# Sheet1.net
KiCad netlist of a schematic drawn in Altium Designer
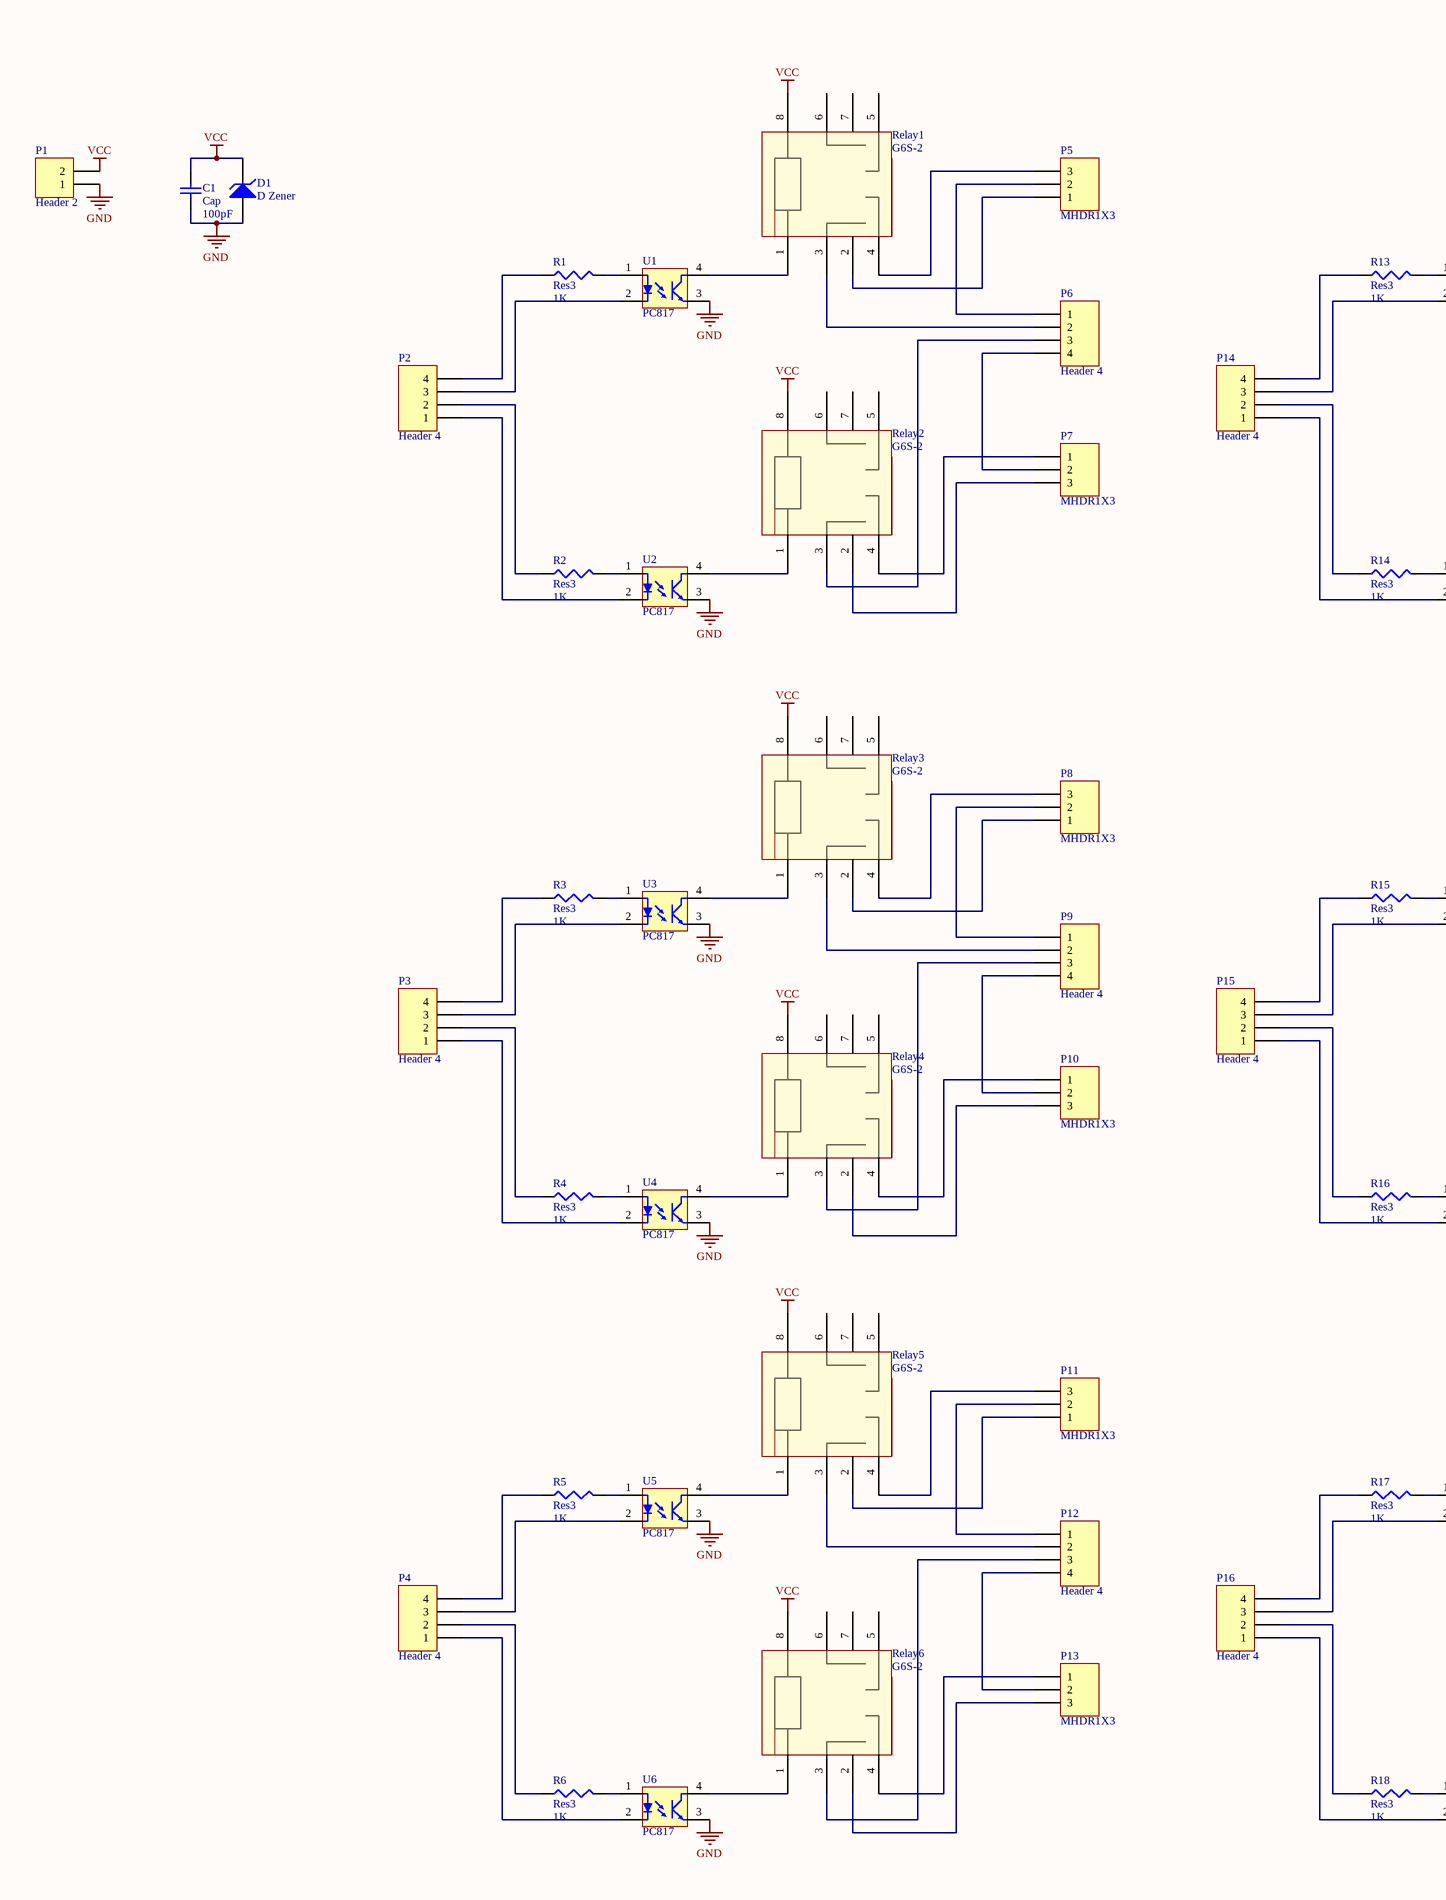
[diagram p0: Sheet1.SchDoc, left]
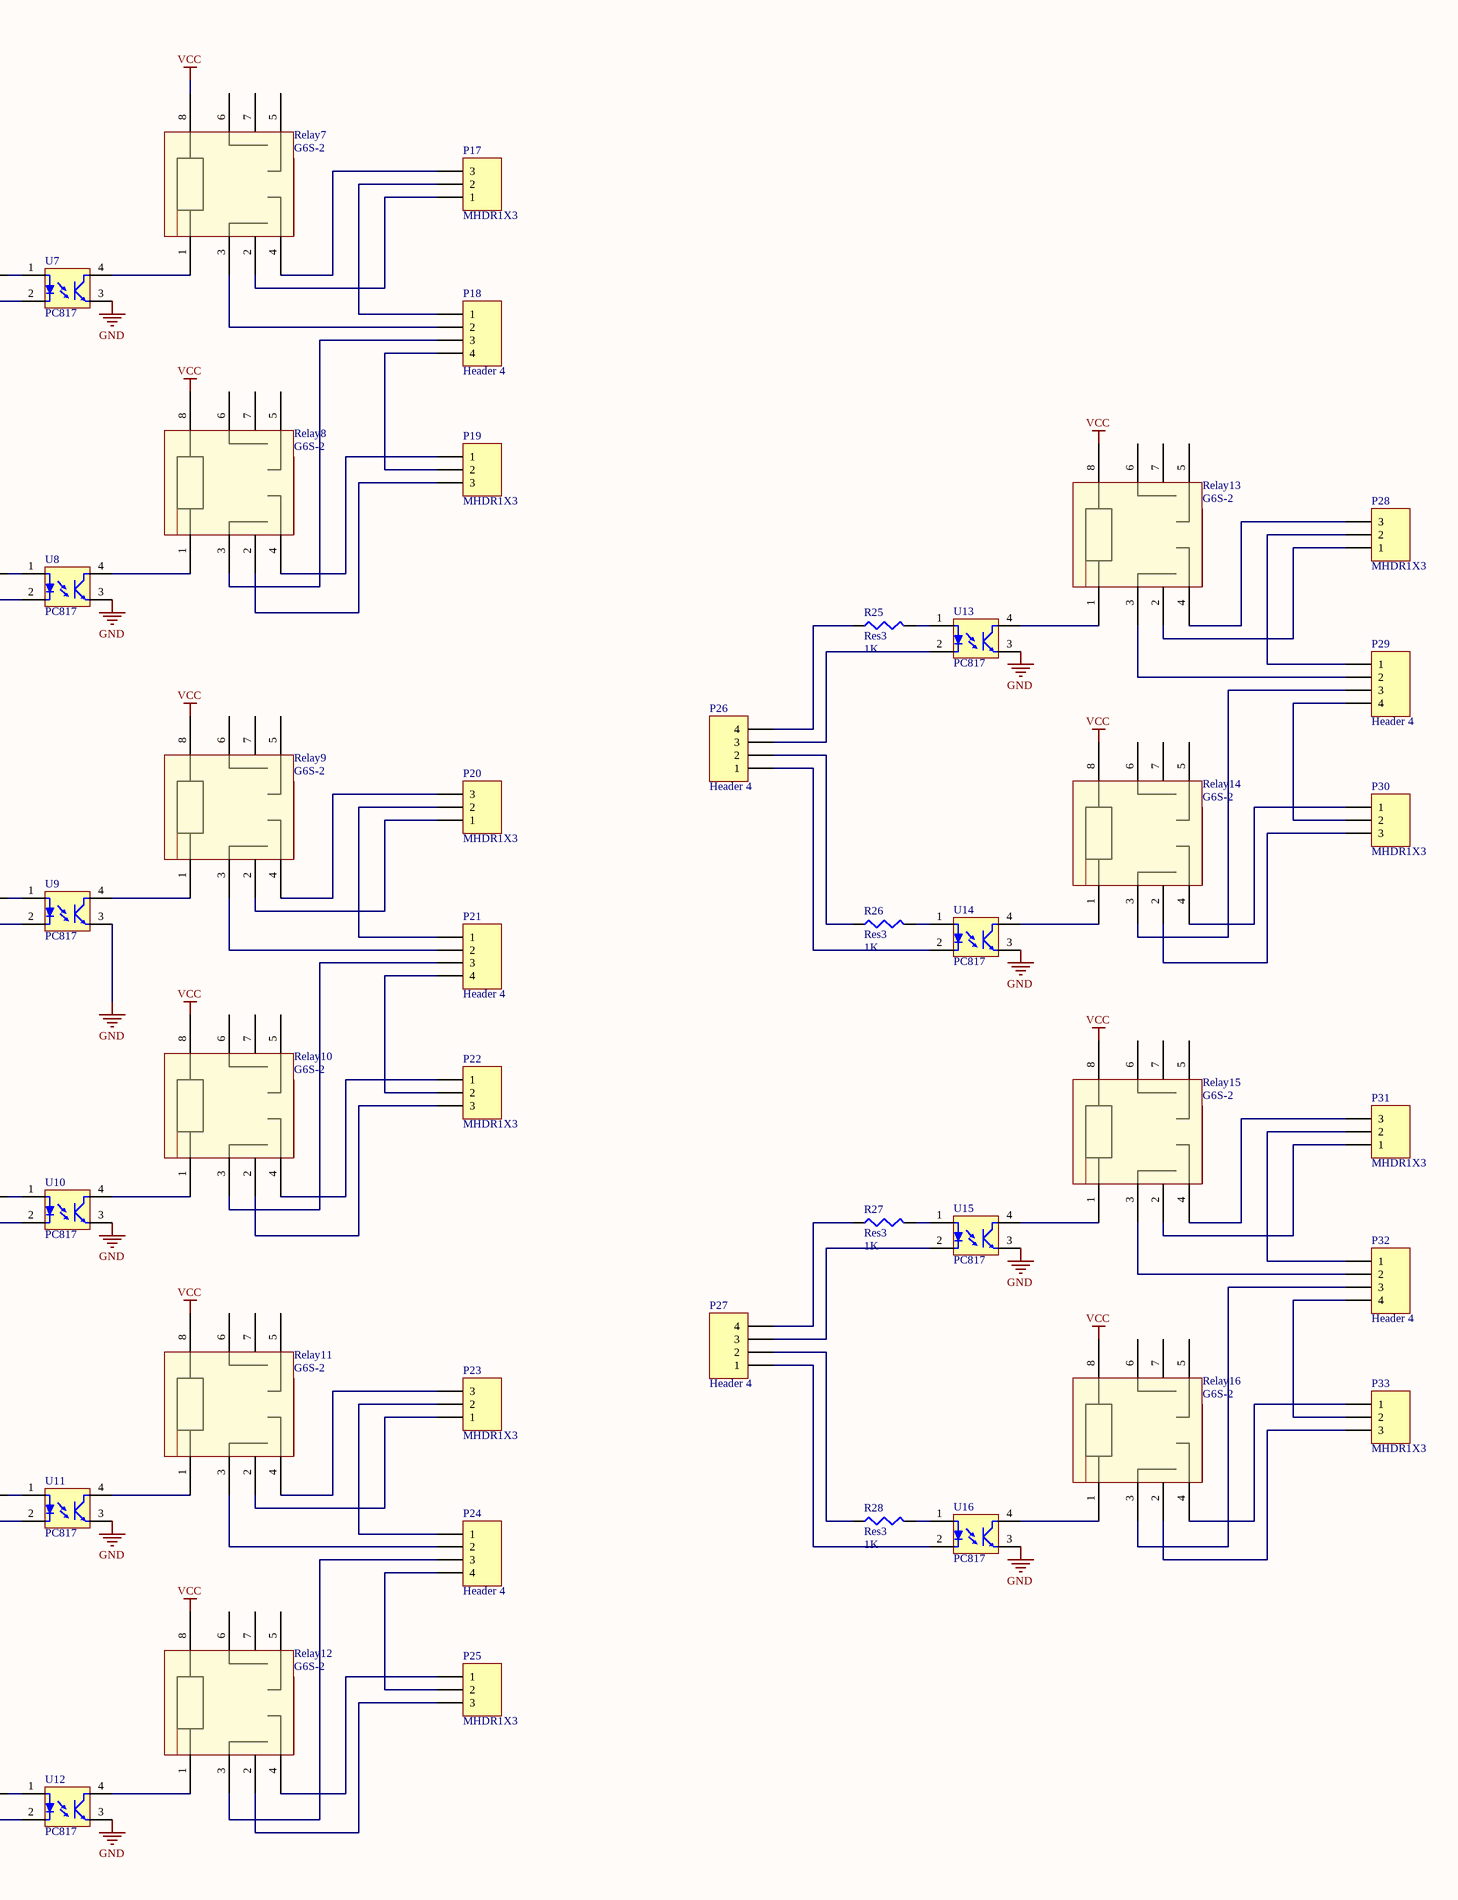
[diagram p1: Sheet1.SchDoc, right]

(export (version "E")
  (design (tool "Eeschema 10.0.6"))
  (components
    (comp (ref "C1")
      (value "Cap")
      (footprint "RAD-0.3")
      (description "Capacitor")
      (fields (field (name "ALTIUM_VALUE") "100pF") (field (name "PUBLISHER") "Altium Limited"))
      (libsource (lib "Miscellaneous Devices") (part "Cap"))
    )
    (comp (ref "D1")
      (value "D Zener")
      (footprint "DIODE-0.7")
      (description "Zener Diode")
      (fields (field (name "PUBLISHER") "Altium Limited"))
      (libsource (lib "Miscellaneous Devices") (part "D Zener"))
    )
    (comp (ref "P1")
      (value "Header 2")
      (footprint "CON2")
      (description "Header, 2-Pin")
      (fields (field (name "PUBLISHER") "Altium Limited"))
      (libsource (lib "Miscellaneous Connectors") (part "Header 2"))
    )
    (comp (ref "P2")
      (value "Header 4")
      (footprint "CON4")
      (description "Header, 4-Pin")
      (fields (field (name "PUBLISHER") "Altium Limited"))
      (libsource (lib "Miscellaneous Connectors") (part "Header 4"))
    )
    (comp (ref "P3")
      (value "Header 4")
      (footprint "CON4")
      (description "Header, 4-Pin")
      (fields (field (name "PUBLISHER") "Altium Limited"))
      (libsource (lib "Miscellaneous Connectors") (part "Header 4"))
    )
    (comp (ref "P4")
      (value "Header 4")
      (footprint "CON4")
      (description "Header, 4-Pin")
      (fields (field (name "PUBLISHER") "Altium Limited"))
      (libsource (lib "Miscellaneous Connectors") (part "Header 4"))
    )
    (comp (ref "P5")
      (value "MHDR1X3")
      (footprint "HDR1X3")
      (description "Header, 3-Pin")
      (fields (field (name "PUBLISHER") "Altium Limited"))
      (libsource (lib "Miscellaneous Connectors") (part "MHDR1X3"))
    )
    (comp (ref "P6")
      (value "Header 4")
      (footprint "CON4")
      (description "Header, 4-Pin")
      (fields (field (name "PUBLISHER") "Altium Limited"))
      (libsource (lib "") (part "Header 4_1"))
    )
    (comp (ref "P7")
      (value "MHDR1X3")
      (footprint "HDR1X3")
      (description "Header, 3-Pin")
      (fields (field (name "PUBLISHER") "Altium Limited"))
      (libsource (lib "") (part "MHDR1X3_1"))
    )
    (comp (ref "P8")
      (value "MHDR1X3")
      (footprint "HDR1X3")
      (description "Header, 3-Pin")
      (fields (field (name "PUBLISHER") "Altium Limited"))
      (libsource (lib "Miscellaneous Connectors") (part "MHDR1X3"))
    )
    (comp (ref "P9")
      (value "Header 4")
      (footprint "CON4")
      (description "Header, 4-Pin")
      (fields (field (name "PUBLISHER") "Altium Limited"))
      (libsource (lib "") (part "Header 4_1"))
    )
    (comp (ref "P10")
      (value "MHDR1X3")
      (footprint "HDR1X3")
      (description "Header, 3-Pin")
      (fields (field (name "PUBLISHER") "Altium Limited"))
      (libsource (lib "") (part "MHDR1X3_1"))
    )
    (comp (ref "P11")
      (value "MHDR1X3")
      (footprint "HDR1X3")
      (description "Header, 3-Pin")
      (fields (field (name "PUBLISHER") "Altium Limited"))
      (libsource (lib "Miscellaneous Connectors") (part "MHDR1X3"))
    )
    (comp (ref "P12")
      (value "Header 4")
      (footprint "CON4")
      (description "Header, 4-Pin")
      (fields (field (name "PUBLISHER") "Altium Limited"))
      (libsource (lib "") (part "Header 4_1"))
    )
    (comp (ref "P13")
      (value "MHDR1X3")
      (footprint "HDR1X3")
      (description "Header, 3-Pin")
      (fields (field (name "PUBLISHER") "Altium Limited"))
      (libsource (lib "") (part "MHDR1X3_1"))
    )
    (comp (ref "P14")
      (value "Header 4")
      (footprint "CON4")
      (description "Header, 4-Pin")
      (fields (field (name "PUBLISHER") "Altium Limited"))
      (libsource (lib "Miscellaneous Connectors") (part "Header 4"))
    )
    (comp (ref "P15")
      (value "Header 4")
      (footprint "CON4")
      (description "Header, 4-Pin")
      (fields (field (name "PUBLISHER") "Altium Limited"))
      (libsource (lib "Miscellaneous Connectors") (part "Header 4"))
    )
    (comp (ref "P16")
      (value "Header 4")
      (footprint "CON4")
      (description "Header, 4-Pin")
      (fields (field (name "PUBLISHER") "Altium Limited"))
      (libsource (lib "Miscellaneous Connectors") (part "Header 4"))
    )
    (comp (ref "P17")
      (value "MHDR1X3")
      (footprint "HDR1X3")
      (description "Header, 3-Pin")
      (fields (field (name "PUBLISHER") "Altium Limited"))
      (libsource (lib "Miscellaneous Connectors") (part "MHDR1X3"))
    )
    (comp (ref "P18")
      (value "Header 4")
      (footprint "CON4")
      (description "Header, 4-Pin")
      (fields (field (name "PUBLISHER") "Altium Limited"))
      (libsource (lib "") (part "Header 4_1"))
    )
    (comp (ref "P19")
      (value "MHDR1X3")
      (footprint "HDR1X3")
      (description "Header, 3-Pin")
      (fields (field (name "PUBLISHER") "Altium Limited"))
      (libsource (lib "") (part "MHDR1X3_1"))
    )
    (comp (ref "P20")
      (value "MHDR1X3")
      (footprint "HDR1X3")
      (description "Header, 3-Pin")
      (fields (field (name "PUBLISHER") "Altium Limited"))
      (libsource (lib "Miscellaneous Connectors") (part "MHDR1X3"))
    )
    (comp (ref "P21")
      (value "Header 4")
      (footprint "CON4")
      (description "Header, 4-Pin")
      (fields (field (name "PUBLISHER") "Altium Limited"))
      (libsource (lib "") (part "Header 4_1"))
    )
    (comp (ref "P22")
      (value "MHDR1X3")
      (footprint "HDR1X3")
      (description "Header, 3-Pin")
      (fields (field (name "PUBLISHER") "Altium Limited"))
      (libsource (lib "") (part "MHDR1X3_1"))
    )
    (comp (ref "P23")
      (value "MHDR1X3")
      (footprint "HDR1X3")
      (description "Header, 3-Pin")
      (fields (field (name "PUBLISHER") "Altium Limited"))
      (libsource (lib "Miscellaneous Connectors") (part "MHDR1X3"))
    )
    (comp (ref "P24")
      (value "Header 4")
      (footprint "CON4")
      (description "Header, 4-Pin")
      (fields (field (name "PUBLISHER") "Altium Limited"))
      (libsource (lib "") (part "Header 4_1"))
    )
    (comp (ref "P25")
      (value "MHDR1X3")
      (footprint "HDR1X3")
      (description "Header, 3-Pin")
      (fields (field (name "PUBLISHER") "Altium Limited"))
      (libsource (lib "") (part "MHDR1X3_1"))
    )
    (comp (ref "P26")
      (value "Header 4")
      (footprint "CON4")
      (description "Header, 4-Pin")
      (fields (field (name "PUBLISHER") "Altium Limited"))
      (libsource (lib "Miscellaneous Connectors") (part "Header 4"))
    )
    (comp (ref "P27")
      (value "Header 4")
      (footprint "CON4")
      (description "Header, 4-Pin")
      (fields (field (name "PUBLISHER") "Altium Limited"))
      (libsource (lib "Miscellaneous Connectors") (part "Header 4"))
    )
    (comp (ref "P28")
      (value "MHDR1X3")
      (footprint "HDR1X3")
      (description "Header, 3-Pin")
      (fields (field (name "PUBLISHER") "Altium Limited"))
      (libsource (lib "Miscellaneous Connectors") (part "MHDR1X3"))
    )
    (comp (ref "P29")
      (value "Header 4")
      (footprint "CON4")
      (description "Header, 4-Pin")
      (fields (field (name "PUBLISHER") "Altium Limited"))
      (libsource (lib "") (part "Header 4_1"))
    )
    (comp (ref "P30")
      (value "MHDR1X3")
      (footprint "HDR1X3")
      (description "Header, 3-Pin")
      (fields (field (name "PUBLISHER") "Altium Limited"))
      (libsource (lib "") (part "MHDR1X3_1"))
    )
    (comp (ref "P31")
      (value "MHDR1X3")
      (footprint "HDR1X3")
      (description "Header, 3-Pin")
      (fields (field (name "PUBLISHER") "Altium Limited"))
      (libsource (lib "Miscellaneous Connectors") (part "MHDR1X3"))
    )
    (comp (ref "P32")
      (value "Header 4")
      (footprint "CON4")
      (description "Header, 4-Pin")
      (fields (field (name "PUBLISHER") "Altium Limited"))
      (libsource (lib "") (part "Header 4_1"))
    )
    (comp (ref "P33")
      (value "MHDR1X3")
      (footprint "HDR1X3")
      (description "Header, 3-Pin")
      (fields (field (name "PUBLISHER") "Altium Limited"))
      (libsource (lib "") (part "MHDR1X3_1"))
    )
    (comp (ref "R1")
      (value "Res3")
      (footprint "R1/4W")
      (description "Resistor")
      (fields (field (name "ALTIUM_VALUE") "1K") (field (name "PUBLISHER") "Altium Limited"))
      (libsource (lib "Miscellaneous Devices") (part "Res3"))
    )
    (comp (ref "R2")
      (value "Res3")
      (footprint "R1/4W")
      (description "Resistor")
      (fields (field (name "ALTIUM_VALUE") "1K") (field (name "PUBLISHER") "Altium Limited"))
      (libsource (lib "Miscellaneous Devices") (part "Res3"))
    )
    (comp (ref "R3")
      (value "Res3")
      (footprint "R1/4W")
      (description "Resistor")
      (fields (field (name "ALTIUM_VALUE") "1K") (field (name "PUBLISHER") "Altium Limited"))
      (libsource (lib "Miscellaneous Devices") (part "Res3"))
    )
    (comp (ref "R4")
      (value "Res3")
      (footprint "R1/4W")
      (description "Resistor")
      (fields (field (name "ALTIUM_VALUE") "1K") (field (name "PUBLISHER") "Altium Limited"))
      (libsource (lib "Miscellaneous Devices") (part "Res3"))
    )
    (comp (ref "R5")
      (value "Res3")
      (footprint "R1/4W")
      (description "Resistor")
      (fields (field (name "ALTIUM_VALUE") "1K") (field (name "PUBLISHER") "Altium Limited"))
      (libsource (lib "Miscellaneous Devices") (part "Res3"))
    )
    (comp (ref "R6")
      (value "Res3")
      (footprint "R1/4W")
      (description "Resistor")
      (fields (field (name "ALTIUM_VALUE") "1K") (field (name "PUBLISHER") "Altium Limited"))
      (libsource (lib "Miscellaneous Devices") (part "Res3"))
    )
    (comp (ref "R13")
      (value "Res3")
      (footprint "R1/4W")
      (description "Resistor")
      (fields (field (name "ALTIUM_VALUE") "1K") (field (name "PUBLISHER") "Altium Limited"))
      (libsource (lib "Miscellaneous Devices") (part "Res3"))
    )
    (comp (ref "R14")
      (value "Res3")
      (footprint "R1/4W")
      (description "Resistor")
      (fields (field (name "ALTIUM_VALUE") "1K") (field (name "PUBLISHER") "Altium Limited"))
      (libsource (lib "Miscellaneous Devices") (part "Res3"))
    )
    (comp (ref "R15")
      (value "Res3")
      (footprint "R1/4W")
      (description "Resistor")
      (fields (field (name "ALTIUM_VALUE") "1K") (field (name "PUBLISHER") "Altium Limited"))
      (libsource (lib "Miscellaneous Devices") (part "Res3"))
    )
    (comp (ref "R16")
      (value "Res3")
      (footprint "R1/4W")
      (description "Resistor")
      (fields (field (name "ALTIUM_VALUE") "1K") (field (name "PUBLISHER") "Altium Limited"))
      (libsource (lib "Miscellaneous Devices") (part "Res3"))
    )
    (comp (ref "R17")
      (value "Res3")
      (footprint "R1/4W")
      (description "Resistor")
      (fields (field (name "ALTIUM_VALUE") "1K") (field (name "PUBLISHER") "Altium Limited"))
      (libsource (lib "Miscellaneous Devices") (part "Res3"))
    )
    (comp (ref "R18")
      (value "Res3")
      (footprint "R1/4W")
      (description "Resistor")
      (fields (field (name "ALTIUM_VALUE") "1K") (field (name "PUBLISHER") "Altium Limited"))
      (libsource (lib "Miscellaneous Devices") (part "Res3"))
    )
    (comp (ref "R25")
      (value "Res3")
      (footprint "R1/4W")
      (description "Resistor")
      (fields (field (name "ALTIUM_VALUE") "1K") (field (name "PUBLISHER") "Altium Limited"))
      (libsource (lib "Miscellaneous Devices") (part "Res3"))
    )
    (comp (ref "R26")
      (value "Res3")
      (footprint "R1/4W")
      (description "Resistor")
      (fields (field (name "ALTIUM_VALUE") "1K") (field (name "PUBLISHER") "Altium Limited"))
      (libsource (lib "Miscellaneous Devices") (part "Res3"))
    )
    (comp (ref "R27")
      (value "Res3")
      (footprint "R1/4W")
      (description "Resistor")
      (fields (field (name "ALTIUM_VALUE") "1K") (field (name "PUBLISHER") "Altium Limited"))
      (libsource (lib "Miscellaneous Devices") (part "Res3"))
    )
    (comp (ref "R28")
      (value "Res3")
      (footprint "R1/4W")
      (description "Resistor")
      (fields (field (name "ALTIUM_VALUE") "1K") (field (name "PUBLISHER") "Altium Limited"))
      (libsource (lib "Miscellaneous Devices") (part "Res3"))
    )
    (comp (ref "Relay1")
      (value "G6S-2")
      (footprint "G6S-2")
      (libsource (lib "dung_maker_2018") (part "G6S-2"))
    )
    (comp (ref "Relay2")
      (value "G6S-2")
      (footprint "G6S-2")
      (libsource (lib "dung_maker_2018") (part "G6S-2"))
    )
    (comp (ref "Relay3")
      (value "G6S-2")
      (footprint "G6S-2")
      (libsource (lib "dung_maker_2018") (part "G6S-2"))
    )
    (comp (ref "Relay4")
      (value "G6S-2")
      (footprint "G6S-2")
      (libsource (lib "dung_maker_2018") (part "G6S-2"))
    )
    (comp (ref "Relay5")
      (value "G6S-2")
      (footprint "G6S-2")
      (libsource (lib "dung_maker_2018") (part "G6S-2"))
    )
    (comp (ref "Relay6")
      (value "G6S-2")
      (footprint "G6S-2")
      (libsource (lib "dung_maker_2018") (part "G6S-2"))
    )
    (comp (ref "Relay7")
      (value "G6S-2")
      (footprint "G6S-2")
      (libsource (lib "dung_maker_2018") (part "G6S-2"))
    )
    (comp (ref "Relay8")
      (value "G6S-2")
      (footprint "G6S-2")
      (libsource (lib "dung_maker_2018") (part "G6S-2"))
    )
    (comp (ref "Relay9")
      (value "G6S-2")
      (footprint "G6S-2")
      (libsource (lib "dung_maker_2018") (part "G6S-2"))
    )
    (comp (ref "Relay10")
      (value "G6S-2")
      (footprint "G6S-2")
      (libsource (lib "dung_maker_2018") (part "G6S-2"))
    )
    (comp (ref "Relay11")
      (value "G6S-2")
      (footprint "G6S-2")
      (libsource (lib "dung_maker_2018") (part "G6S-2"))
    )
    (comp (ref "Relay12")
      (value "G6S-2")
      (footprint "G6S-2")
      (libsource (lib "dung_maker_2018") (part "G6S-2"))
    )
    (comp (ref "Relay13")
      (value "G6S-2")
      (footprint "G6S-2")
      (libsource (lib "dung_maker_2018") (part "G6S-2"))
    )
    (comp (ref "Relay14")
      (value "G6S-2")
      (footprint "G6S-2")
      (libsource (lib "dung_maker_2018") (part "G6S-2"))
    )
    (comp (ref "Relay15")
      (value "G6S-2")
      (footprint "G6S-2")
      (libsource (lib "dung_maker_2018") (part "G6S-2"))
    )
    (comp (ref "Relay16")
      (value "G6S-2")
      (footprint "G6S-2")
      (libsource (lib "dung_maker_2018") (part "G6S-2"))
    )
    (comp (ref "U1")
      (value "PC817")
      (footprint "DIP4")
      (fields (field (name "Comment") "OPTO"))
      (libsource (lib "dung_maker_2018") (part "OPTO_PC817"))
    )
    (comp (ref "U2")
      (value "PC817")
      (footprint "DIP4")
      (fields (field (name "Comment") "OPTO"))
      (libsource (lib "dung_maker_2018") (part "OPTO_PC817"))
    )
    (comp (ref "U3")
      (value "PC817")
      (footprint "DIP4")
      (fields (field (name "Comment") "OPTO"))
      (libsource (lib "dung_maker_2018") (part "OPTO_PC817"))
    )
    (comp (ref "U4")
      (value "PC817")
      (footprint "DIP4")
      (fields (field (name "Comment") "OPTO"))
      (libsource (lib "dung_maker_2018") (part "OPTO_PC817"))
    )
    (comp (ref "U5")
      (value "PC817")
      (footprint "DIP4")
      (fields (field (name "Comment") "OPTO"))
      (libsource (lib "dung_maker_2018") (part "OPTO_PC817"))
    )
    (comp (ref "U6")
      (value "PC817")
      (footprint "DIP4")
      (fields (field (name "Comment") "OPTO"))
      (libsource (lib "dung_maker_2018") (part "OPTO_PC817"))
    )
    (comp (ref "U7")
      (value "PC817")
      (footprint "DIP4")
      (fields (field (name "Comment") "OPTO"))
      (libsource (lib "dung_maker_2018") (part "OPTO_PC817"))
    )
    (comp (ref "U8")
      (value "PC817")
      (footprint "DIP4")
      (fields (field (name "Comment") "OPTO"))
      (libsource (lib "dung_maker_2018") (part "OPTO_PC817"))
    )
    (comp (ref "U9")
      (value "PC817")
      (footprint "DIP4")
      (fields (field (name "Comment") "OPTO"))
      (libsource (lib "dung_maker_2018") (part "OPTO_PC817"))
    )
    (comp (ref "U10")
      (value "PC817")
      (footprint "DIP4")
      (fields (field (name "Comment") "OPTO"))
      (libsource (lib "dung_maker_2018") (part "OPTO_PC817"))
    )
    (comp (ref "U11")
      (value "PC817")
      (footprint "DIP4")
      (fields (field (name "Comment") "OPTO"))
      (libsource (lib "dung_maker_2018") (part "OPTO_PC817"))
    )
    (comp (ref "U12")
      (value "PC817")
      (footprint "DIP4")
      (fields (field (name "Comment") "OPTO"))
      (libsource (lib "dung_maker_2018") (part "OPTO_PC817"))
    )
    (comp (ref "U13")
      (value "PC817")
      (footprint "DIP4")
      (fields (field (name "Comment") "OPTO"))
      (libsource (lib "dung_maker_2018") (part "OPTO_PC817"))
    )
    (comp (ref "U14")
      (value "PC817")
      (footprint "DIP4")
      (fields (field (name "Comment") "OPTO"))
      (libsource (lib "dung_maker_2018") (part "OPTO_PC817"))
    )
    (comp (ref "U15")
      (value "PC817")
      (footprint "DIP4")
      (fields (field (name "Comment") "OPTO"))
      (libsource (lib "dung_maker_2018") (part "OPTO_PC817"))
    )
    (comp (ref "U16")
      (value "PC817")
      (footprint "DIP4")
      (fields (field (name "Comment") "OPTO"))
      (libsource (lib "dung_maker_2018") (part "OPTO_PC817"))
    )
  )
  (nets
    (net (code "1") (name "GND") (class "Default")
      (node (ref "C1") (pin "1") (pinfunction "1_1") (pintype "passive"))
      (node (ref "D1") (pin "1") (pinfunction "A_1") (pintype "passive"))
      (node (ref "P1") (pin "1") (pinfunction "1_1") (pintype "passive"))
      (node (ref "U1") (pin "3") (pinfunction "E_3") (pintype "passive"))
      (node (ref "U10") (pin "3") (pinfunction "E_3") (pintype "passive"))
      (node (ref "U11") (pin "3") (pinfunction "E_3") (pintype "passive"))
      (node (ref "U12") (pin "3") (pinfunction "E_3") (pintype "passive"))
      (node (ref "U13") (pin "3") (pinfunction "E_3") (pintype "passive"))
      (node (ref "U14") (pin "3") (pinfunction "E_3") (pintype "passive"))
      (node (ref "U15") (pin "3") (pinfunction "E_3") (pintype "passive"))
      (node (ref "U16") (pin "3") (pinfunction "E_3") (pintype "passive"))
      (node (ref "U2") (pin "3") (pinfunction "E_3") (pintype "passive"))
      (node (ref "U3") (pin "3") (pinfunction "E_3") (pintype "passive"))
      (node (ref "U4") (pin "3") (pinfunction "E_3") (pintype "passive"))
      (node (ref "U5") (pin "3") (pinfunction "E_3") (pintype "passive"))
      (node (ref "U6") (pin "3") (pinfunction "E_3") (pintype "passive"))
      (node (ref "U7") (pin "3") (pinfunction "E_3") (pintype "passive"))
      (node (ref "U8") (pin "3") (pinfunction "E_3") (pintype "passive"))
      (node (ref "U9") (pin "3") (pinfunction "E_3") (pintype "passive"))
    )
    (net (code "2") (name "Net-(P2-Pad1)") (class "Default")
      (node (ref "P2") (pin "1") (pinfunction "1_1") (pintype "passive"))
      (node (ref "U2") (pin "2") (pinfunction "C_2") (pintype "passive"))
    )
    (net (code "3") (name "Net-(P2-Pad2)") (class "Default")
      (node (ref "P2") (pin "2") (pinfunction "2_2") (pintype "passive"))
      (node (ref "R2") (pin "1") (pinfunction "1_1") (pintype "passive"))
    )
    (net (code "4") (name "Net-(P2-Pad3)") (class "Default")
      (node (ref "P2") (pin "3") (pinfunction "3_3") (pintype "passive"))
      (node (ref "U1") (pin "2") (pinfunction "C_2") (pintype "passive"))
    )
    (net (code "5") (name "Net-(P2-Pad4)") (class "Default")
      (node (ref "P2") (pin "4") (pinfunction "4_4") (pintype "passive"))
      (node (ref "R1") (pin "1") (pinfunction "1_1") (pintype "passive"))
    )
    (net (code "6") (name "Net-(P3-Pad1)") (class "Default")
      (node (ref "P3") (pin "1") (pinfunction "1_1") (pintype "passive"))
      (node (ref "U4") (pin "2") (pinfunction "C_2") (pintype "passive"))
    )
    (net (code "7") (name "Net-(P3-Pad2)") (class "Default")
      (node (ref "P3") (pin "2") (pinfunction "2_2") (pintype "passive"))
      (node (ref "R4") (pin "1") (pinfunction "1_1") (pintype "passive"))
    )
    (net (code "8") (name "Net-(P3-Pad3)") (class "Default")
      (node (ref "P3") (pin "3") (pinfunction "3_3") (pintype "passive"))
      (node (ref "U3") (pin "2") (pinfunction "C_2") (pintype "passive"))
    )
    (net (code "9") (name "Net-(P3-Pad4)") (class "Default")
      (node (ref "P3") (pin "4") (pinfunction "4_4") (pintype "passive"))
      (node (ref "R3") (pin "1") (pinfunction "1_1") (pintype "passive"))
    )
    (net (code "10") (name "Net-(P4-Pad1)") (class "Default")
      (node (ref "P4") (pin "1") (pinfunction "1_1") (pintype "passive"))
      (node (ref "U6") (pin "2") (pinfunction "C_2") (pintype "passive"))
    )
    (net (code "11") (name "Net-(P4-Pad2)") (class "Default")
      (node (ref "P4") (pin "2") (pinfunction "2_2") (pintype "passive"))
      (node (ref "R6") (pin "1") (pinfunction "1_1") (pintype "passive"))
    )
    (net (code "12") (name "Net-(P4-Pad3)") (class "Default")
      (node (ref "P4") (pin "3") (pinfunction "3_3") (pintype "passive"))
      (node (ref "U5") (pin "2") (pinfunction "C_2") (pintype "passive"))
    )
    (net (code "13") (name "Net-(P4-Pad4)") (class "Default")
      (node (ref "P4") (pin "4") (pinfunction "4_4") (pintype "passive"))
      (node (ref "R5") (pin "1") (pinfunction "1_1") (pintype "passive"))
    )
    (net (code "14") (name "Net-(P5-Pad2)") (class "Default")
      (node (ref "P5") (pin "2") (pinfunction "2_2") (pintype "passive"))
      (node (ref "P6") (pin "1") (pinfunction "1_1") (pintype "passive"))
    )
    (net (code "15") (name "Net-(P6-Pad2)") (class "Default")
      (node (ref "P6") (pin "2") (pinfunction "2_2") (pintype "passive"))
      (node (ref "Relay1") (pin "3") (pinfunction "3_3") (pintype "passive"))
    )
    (net (code "16") (name "Net-(P6-Pad3)") (class "Default")
      (node (ref "P6") (pin "3") (pinfunction "3_3") (pintype "passive"))
      (node (ref "Relay2") (pin "3") (pinfunction "3_3") (pintype "passive"))
    )
    (net (code "17") (name "Net-(P6-Pad4)") (class "Default")
      (node (ref "P6") (pin "4") (pinfunction "4_4") (pintype "passive"))
      (node (ref "P7") (pin "2") (pinfunction "2_2") (pintype "passive"))
    )
    (net (code "18") (name "Net-(P8-Pad2)") (class "Default")
      (node (ref "P8") (pin "2") (pinfunction "2_2") (pintype "passive"))
      (node (ref "P9") (pin "1") (pinfunction "1_1") (pintype "passive"))
    )
    (net (code "19") (name "Net-(P9-Pad2)") (class "Default")
      (node (ref "P9") (pin "2") (pinfunction "2_2") (pintype "passive"))
      (node (ref "Relay3") (pin "3") (pinfunction "3_3") (pintype "passive"))
    )
    (net (code "20") (name "Net-(P9-Pad3)") (class "Default")
      (node (ref "P9") (pin "3") (pinfunction "3_3") (pintype "passive"))
      (node (ref "Relay4") (pin "3") (pinfunction "3_3") (pintype "passive"))
    )
    (net (code "21") (name "Net-(P10-Pad2)") (class "Default")
      (node (ref "P10") (pin "2") (pinfunction "2_2") (pintype "passive"))
      (node (ref "P9") (pin "4") (pinfunction "4_4") (pintype "passive"))
    )
    (net (code "22") (name "Net-(P11-Pad2)") (class "Default")
      (node (ref "P11") (pin "2") (pinfunction "2_2") (pintype "passive"))
      (node (ref "P12") (pin "1") (pinfunction "1_1") (pintype "passive"))
    )
    (net (code "23") (name "Net-(P12-Pad2)") (class "Default")
      (node (ref "P12") (pin "2") (pinfunction "2_2") (pintype "passive"))
      (node (ref "Relay5") (pin "3") (pinfunction "3_3") (pintype "passive"))
    )
    (net (code "24") (name "Net-(P12-Pad3)") (class "Default")
      (node (ref "P12") (pin "3") (pinfunction "3_3") (pintype "passive"))
      (node (ref "Relay6") (pin "3") (pinfunction "3_3") (pintype "passive"))
    )
    (net (code "25") (name "Net-(P12-Pad4)") (class "Default")
      (node (ref "P12") (pin "4") (pinfunction "4_4") (pintype "passive"))
      (node (ref "P13") (pin "2") (pinfunction "2_2") (pintype "passive"))
    )
    (net (code "26") (name "Net-(P14-Pad1)") (class "Default")
      (node (ref "P14") (pin "1") (pinfunction "1_1") (pintype "passive"))
      (node (ref "U8") (pin "2") (pinfunction "C_2") (pintype "passive"))
    )
    (net (code "27") (name "Net-(P14-Pad2)") (class "Default")
      (node (ref "P14") (pin "2") (pinfunction "2_2") (pintype "passive"))
      (node (ref "R14") (pin "1") (pinfunction "1_1") (pintype "passive"))
    )
    (net (code "28") (name "Net-(P14-Pad3)") (class "Default")
      (node (ref "P14") (pin "3") (pinfunction "3_3") (pintype "passive"))
      (node (ref "U7") (pin "2") (pinfunction "C_2") (pintype "passive"))
    )
    (net (code "29") (name "Net-(P14-Pad4)") (class "Default")
      (node (ref "P14") (pin "4") (pinfunction "4_4") (pintype "passive"))
      (node (ref "R13") (pin "1") (pinfunction "1_1") (pintype "passive"))
    )
    (net (code "30") (name "Net-(P15-Pad1)") (class "Default")
      (node (ref "P15") (pin "1") (pinfunction "1_1") (pintype "passive"))
      (node (ref "U10") (pin "2") (pinfunction "C_2") (pintype "passive"))
    )
    (net (code "31") (name "Net-(P15-Pad2)") (class "Default")
      (node (ref "P15") (pin "2") (pinfunction "2_2") (pintype "passive"))
      (node (ref "R16") (pin "1") (pinfunction "1_1") (pintype "passive"))
    )
    (net (code "32") (name "Net-(P15-Pad3)") (class "Default")
      (node (ref "P15") (pin "3") (pinfunction "3_3") (pintype "passive"))
      (node (ref "U9") (pin "2") (pinfunction "C_2") (pintype "passive"))
    )
    (net (code "33") (name "Net-(P15-Pad4)") (class "Default")
      (node (ref "P15") (pin "4") (pinfunction "4_4") (pintype "passive"))
      (node (ref "R15") (pin "1") (pinfunction "1_1") (pintype "passive"))
    )
    (net (code "34") (name "Net-(P16-Pad1)") (class "Default")
      (node (ref "P16") (pin "1") (pinfunction "1_1") (pintype "passive"))
      (node (ref "U12") (pin "2") (pinfunction "C_2") (pintype "passive"))
    )
    (net (code "35") (name "Net-(P16-Pad2)") (class "Default")
      (node (ref "P16") (pin "2") (pinfunction "2_2") (pintype "passive"))
      (node (ref "R18") (pin "1") (pinfunction "1_1") (pintype "passive"))
    )
    (net (code "36") (name "Net-(P16-Pad3)") (class "Default")
      (node (ref "P16") (pin "3") (pinfunction "3_3") (pintype "passive"))
      (node (ref "U11") (pin "2") (pinfunction "C_2") (pintype "passive"))
    )
    (net (code "37") (name "Net-(P16-Pad4)") (class "Default")
      (node (ref "P16") (pin "4") (pinfunction "4_4") (pintype "passive"))
      (node (ref "R17") (pin "1") (pinfunction "1_1") (pintype "passive"))
    )
    (net (code "38") (name "Net-(P17-Pad2)") (class "Default")
      (node (ref "P17") (pin "2") (pinfunction "2_2") (pintype "passive"))
      (node (ref "P18") (pin "1") (pinfunction "1_1") (pintype "passive"))
    )
    (net (code "39") (name "Net-(P18-Pad2)") (class "Default")
      (node (ref "P18") (pin "2") (pinfunction "2_2") (pintype "passive"))
      (node (ref "Relay7") (pin "3") (pinfunction "3_3") (pintype "passive"))
    )
    (net (code "40") (name "Net-(P18-Pad3)") (class "Default")
      (node (ref "P18") (pin "3") (pinfunction "3_3") (pintype "passive"))
      (node (ref "Relay8") (pin "3") (pinfunction "3_3") (pintype "passive"))
    )
    (net (code "41") (name "Net-(P18-Pad4)") (class "Default")
      (node (ref "P18") (pin "4") (pinfunction "4_4") (pintype "passive"))
      (node (ref "P19") (pin "2") (pinfunction "2_2") (pintype "passive"))
    )
    (net (code "42") (name "Net-(P20-Pad2)") (class "Default")
      (node (ref "P20") (pin "2") (pinfunction "2_2") (pintype "passive"))
      (node (ref "P21") (pin "1") (pinfunction "1_1") (pintype "passive"))
    )
    (net (code "43") (name "Net-(P21-Pad2)") (class "Default")
      (node (ref "P21") (pin "2") (pinfunction "2_2") (pintype "passive"))
      (node (ref "Relay9") (pin "3") (pinfunction "3_3") (pintype "passive"))
    )
    (net (code "44") (name "Net-(P21-Pad3)") (class "Default")
      (node (ref "P21") (pin "3") (pinfunction "3_3") (pintype "passive"))
      (node (ref "Relay10") (pin "3") (pinfunction "3_3") (pintype "passive"))
    )
    (net (code "45") (name "Net-(P21-Pad4)") (class "Default")
      (node (ref "P21") (pin "4") (pinfunction "4_4") (pintype "passive"))
      (node (ref "P22") (pin "2") (pinfunction "2_2") (pintype "passive"))
    )
    (net (code "46") (name "Net-(P23-Pad2)") (class "Default")
      (node (ref "P23") (pin "2") (pinfunction "2_2") (pintype "passive"))
      (node (ref "P24") (pin "1") (pinfunction "1_1") (pintype "passive"))
    )
    (net (code "47") (name "Net-(P24-Pad2)") (class "Default")
      (node (ref "P24") (pin "2") (pinfunction "2_2") (pintype "passive"))
      (node (ref "Relay11") (pin "3") (pinfunction "3_3") (pintype "passive"))
    )
    (net (code "48") (name "Net-(P24-Pad3)") (class "Default")
      (node (ref "P24") (pin "3") (pinfunction "3_3") (pintype "passive"))
      (node (ref "Relay12") (pin "3") (pinfunction "3_3") (pintype "passive"))
    )
    (net (code "49") (name "Net-(P24-Pad4)") (class "Default")
      (node (ref "P24") (pin "4") (pinfunction "4_4") (pintype "passive"))
      (node (ref "P25") (pin "2") (pinfunction "2_2") (pintype "passive"))
    )
    (net (code "50") (name "Net-(P26-Pad1)") (class "Default")
      (node (ref "P26") (pin "1") (pinfunction "1_1") (pintype "passive"))
      (node (ref "U14") (pin "2") (pinfunction "C_2") (pintype "passive"))
    )
    (net (code "51") (name "Net-(P26-Pad2)") (class "Default")
      (node (ref "P26") (pin "2") (pinfunction "2_2") (pintype "passive"))
      (node (ref "R26") (pin "1") (pinfunction "1_1") (pintype "passive"))
    )
    (net (code "52") (name "Net-(P26-Pad3)") (class "Default")
      (node (ref "P26") (pin "3") (pinfunction "3_3") (pintype "passive"))
      (node (ref "U13") (pin "2") (pinfunction "C_2") (pintype "passive"))
    )
    (net (code "53") (name "Net-(P26-Pad4)") (class "Default")
      (node (ref "P26") (pin "4") (pinfunction "4_4") (pintype "passive"))
      (node (ref "R25") (pin "1") (pinfunction "1_1") (pintype "passive"))
    )
    (net (code "54") (name "Net-(P27-Pad1)") (class "Default")
      (node (ref "P27") (pin "1") (pinfunction "1_1") (pintype "passive"))
      (node (ref "U16") (pin "2") (pinfunction "C_2") (pintype "passive"))
    )
    (net (code "55") (name "Net-(P27-Pad2)") (class "Default")
      (node (ref "P27") (pin "2") (pinfunction "2_2") (pintype "passive"))
      (node (ref "R28") (pin "1") (pinfunction "1_1") (pintype "passive"))
    )
    (net (code "56") (name "Net-(P27-Pad3)") (class "Default")
      (node (ref "P27") (pin "3") (pinfunction "3_3") (pintype "passive"))
      (node (ref "U15") (pin "2") (pinfunction "C_2") (pintype "passive"))
    )
    (net (code "57") (name "Net-(P27-Pad4)") (class "Default")
      (node (ref "P27") (pin "4") (pinfunction "4_4") (pintype "passive"))
      (node (ref "R27") (pin "1") (pinfunction "1_1") (pintype "passive"))
    )
    (net (code "58") (name "Net-(P28-Pad2)") (class "Default")
      (node (ref "P28") (pin "2") (pinfunction "2_2") (pintype "passive"))
      (node (ref "P29") (pin "1") (pinfunction "1_1") (pintype "passive"))
    )
    (net (code "59") (name "Net-(P29-Pad2)") (class "Default")
      (node (ref "P29") (pin "2") (pinfunction "2_2") (pintype "passive"))
      (node (ref "Relay13") (pin "3") (pinfunction "3_3") (pintype "passive"))
    )
    (net (code "60") (name "Net-(P29-Pad3)") (class "Default")
      (node (ref "P29") (pin "3") (pinfunction "3_3") (pintype "passive"))
      (node (ref "Relay14") (pin "3") (pinfunction "3_3") (pintype "passive"))
    )
    (net (code "61") (name "Net-(P29-Pad4)") (class "Default")
      (node (ref "P29") (pin "4") (pinfunction "4_4") (pintype "passive"))
      (node (ref "P30") (pin "2") (pinfunction "2_2") (pintype "passive"))
    )
    (net (code "62") (name "Net-(P31-Pad2)") (class "Default")
      (node (ref "P31") (pin "2") (pinfunction "2_2") (pintype "passive"))
      (node (ref "P32") (pin "1") (pinfunction "1_1") (pintype "passive"))
    )
    (net (code "63") (name "Net-(P32-Pad2)") (class "Default")
      (node (ref "P32") (pin "2") (pinfunction "2_2") (pintype "passive"))
      (node (ref "Relay15") (pin "3") (pinfunction "3_3") (pintype "passive"))
    )
    (net (code "64") (name "Net-(P32-Pad3)") (class "Default")
      (node (ref "P32") (pin "3") (pinfunction "3_3") (pintype "passive"))
      (node (ref "Relay16") (pin "3") (pinfunction "3_3") (pintype "passive"))
    )
    (net (code "65") (name "Net-(P32-Pad4)") (class "Default")
      (node (ref "P32") (pin "4") (pinfunction "4_4") (pintype "passive"))
      (node (ref "P33") (pin "2") (pinfunction "2_2") (pintype "passive"))
    )
    (net (code "66") (name "Net-(Relay1-NC)") (class "Default")
      (node (ref "P5") (pin "1") (pinfunction "1_1") (pintype "passive"))
      (node (ref "Relay1") (pin "2") (pinfunction "NC_2") (pintype "passive"))
    )
    (net (code "67") (name "Net-(Relay1-NO)") (class "Default")
      (node (ref "P5") (pin "3") (pinfunction "3_3") (pintype "passive"))
      (node (ref "Relay1") (pin "4") (pinfunction "NO_4") (pintype "passive"))
    )
    (net (code "68") (name "Net-(Relay1-Pad1)") (class "Default")
      (node (ref "Relay1") (pin "1") (pinfunction "1_1") (pintype "passive"))
      (node (ref "U1") (pin "4") (pinfunction "C_4") (pintype "passive"))
    )
    (net (code "69") (name "Net-(Relay2-NC)") (class "Default")
      (node (ref "P7") (pin "3") (pinfunction "3_3") (pintype "passive"))
      (node (ref "Relay2") (pin "2") (pinfunction "NC_2") (pintype "passive"))
    )
    (net (code "70") (name "Net-(Relay2-NO)") (class "Default")
      (node (ref "P7") (pin "1") (pinfunction "1_1") (pintype "passive"))
      (node (ref "Relay2") (pin "4") (pinfunction "NO_4") (pintype "passive"))
    )
    (net (code "71") (name "Net-(Relay2-Pad1)") (class "Default")
      (node (ref "Relay2") (pin "1") (pinfunction "1_1") (pintype "passive"))
      (node (ref "U2") (pin "4") (pinfunction "C_4") (pintype "passive"))
    )
    (net (code "72") (name "Net-(Relay3-NC)") (class "Default")
      (node (ref "P8") (pin "1") (pinfunction "1_1") (pintype "passive"))
      (node (ref "Relay3") (pin "2") (pinfunction "NC_2") (pintype "passive"))
    )
    (net (code "73") (name "Net-(Relay3-NO)") (class "Default")
      (node (ref "P8") (pin "3") (pinfunction "3_3") (pintype "passive"))
      (node (ref "Relay3") (pin "4") (pinfunction "NO_4") (pintype "passive"))
    )
    (net (code "74") (name "Net-(Relay3-Pad1)") (class "Default")
      (node (ref "Relay3") (pin "1") (pinfunction "1_1") (pintype "passive"))
      (node (ref "U3") (pin "4") (pinfunction "C_4") (pintype "passive"))
    )
    (net (code "75") (name "Net-(Relay4-NC)") (class "Default")
      (node (ref "P10") (pin "3") (pinfunction "3_3") (pintype "passive"))
      (node (ref "Relay4") (pin "2") (pinfunction "NC_2") (pintype "passive"))
    )
    (net (code "76") (name "Net-(Relay4-NO)") (class "Default")
      (node (ref "P10") (pin "1") (pinfunction "1_1") (pintype "passive"))
      (node (ref "Relay4") (pin "4") (pinfunction "NO_4") (pintype "passive"))
    )
    (net (code "77") (name "Net-(Relay4-Pad1)") (class "Default")
      (node (ref "Relay4") (pin "1") (pinfunction "1_1") (pintype "passive"))
      (node (ref "U4") (pin "4") (pinfunction "C_4") (pintype "passive"))
    )
    (net (code "78") (name "Net-(Relay5-NC)") (class "Default")
      (node (ref "P11") (pin "1") (pinfunction "1_1") (pintype "passive"))
      (node (ref "Relay5") (pin "2") (pinfunction "NC_2") (pintype "passive"))
    )
    (net (code "79") (name "Net-(Relay5-NO)") (class "Default")
      (node (ref "P11") (pin "3") (pinfunction "3_3") (pintype "passive"))
      (node (ref "Relay5") (pin "4") (pinfunction "NO_4") (pintype "passive"))
    )
    (net (code "80") (name "Net-(Relay5-Pad1)") (class "Default")
      (node (ref "Relay5") (pin "1") (pinfunction "1_1") (pintype "passive"))
      (node (ref "U5") (pin "4") (pinfunction "C_4") (pintype "passive"))
    )
    (net (code "81") (name "Net-(Relay6-NC)") (class "Default")
      (node (ref "P13") (pin "3") (pinfunction "3_3") (pintype "passive"))
      (node (ref "Relay6") (pin "2") (pinfunction "NC_2") (pintype "passive"))
    )
    (net (code "82") (name "Net-(Relay6-NO)") (class "Default")
      (node (ref "P13") (pin "1") (pinfunction "1_1") (pintype "passive"))
      (node (ref "Relay6") (pin "4") (pinfunction "NO_4") (pintype "passive"))
    )
    (net (code "83") (name "Net-(Relay6-Pad1)") (class "Default")
      (node (ref "Relay6") (pin "1") (pinfunction "1_1") (pintype "passive"))
      (node (ref "U6") (pin "4") (pinfunction "C_4") (pintype "passive"))
    )
    (net (code "84") (name "Net-(Relay7-NC)") (class "Default")
      (node (ref "P17") (pin "1") (pinfunction "1_1") (pintype "passive"))
      (node (ref "Relay7") (pin "2") (pinfunction "NC_2") (pintype "passive"))
    )
    (net (code "85") (name "Net-(Relay7-NO)") (class "Default")
      (node (ref "P17") (pin "3") (pinfunction "3_3") (pintype "passive"))
      (node (ref "Relay7") (pin "4") (pinfunction "NO_4") (pintype "passive"))
    )
    (net (code "86") (name "Net-(Relay7-Pad1)") (class "Default")
      (node (ref "Relay7") (pin "1") (pinfunction "1_1") (pintype "passive"))
      (node (ref "U7") (pin "4") (pinfunction "C_4") (pintype "passive"))
    )
    (net (code "87") (name "Net-(Relay8-NC)") (class "Default")
      (node (ref "P19") (pin "3") (pinfunction "3_3") (pintype "passive"))
      (node (ref "Relay8") (pin "2") (pinfunction "NC_2") (pintype "passive"))
    )
    (net (code "88") (name "Net-(Relay8-NO)") (class "Default")
      (node (ref "P19") (pin "1") (pinfunction "1_1") (pintype "passive"))
      (node (ref "Relay8") (pin "4") (pinfunction "NO_4") (pintype "passive"))
    )
    (net (code "89") (name "Net-(Relay8-Pad1)") (class "Default")
      (node (ref "Relay8") (pin "1") (pinfunction "1_1") (pintype "passive"))
      (node (ref "U8") (pin "4") (pinfunction "C_4") (pintype "passive"))
    )
    (net (code "90") (name "Net-(Relay9-NC)") (class "Default")
      (node (ref "P20") (pin "1") (pinfunction "1_1") (pintype "passive"))
      (node (ref "Relay9") (pin "2") (pinfunction "NC_2") (pintype "passive"))
    )
    (net (code "91") (name "Net-(Relay9-NO)") (class "Default")
      (node (ref "P20") (pin "3") (pinfunction "3_3") (pintype "passive"))
      (node (ref "Relay9") (pin "4") (pinfunction "NO_4") (pintype "passive"))
    )
    (net (code "92") (name "Net-(Relay9-Pad1)") (class "Default")
      (node (ref "Relay9") (pin "1") (pinfunction "1_1") (pintype "passive"))
      (node (ref "U9") (pin "4") (pinfunction "C_4") (pintype "passive"))
    )
    (net (code "93") (name "Net-(Relay10-NC)") (class "Default")
      (node (ref "P22") (pin "3") (pinfunction "3_3") (pintype "passive"))
      (node (ref "Relay10") (pin "2") (pinfunction "NC_2") (pintype "passive"))
    )
    (net (code "94") (name "Net-(Relay10-NO)") (class "Default")
      (node (ref "P22") (pin "1") (pinfunction "1_1") (pintype "passive"))
      (node (ref "Relay10") (pin "4") (pinfunction "NO_4") (pintype "passive"))
    )
    (net (code "95") (name "Net-(Relay10-Pad1)") (class "Default")
      (node (ref "Relay10") (pin "1") (pinfunction "1_1") (pintype "passive"))
      (node (ref "U10") (pin "4") (pinfunction "C_4") (pintype "passive"))
    )
    (net (code "96") (name "Net-(Relay11-NC)") (class "Default")
      (node (ref "P23") (pin "1") (pinfunction "1_1") (pintype "passive"))
      (node (ref "Relay11") (pin "2") (pinfunction "NC_2") (pintype "passive"))
    )
    (net (code "97") (name "Net-(Relay11-NO)") (class "Default")
      (node (ref "P23") (pin "3") (pinfunction "3_3") (pintype "passive"))
      (node (ref "Relay11") (pin "4") (pinfunction "NO_4") (pintype "passive"))
    )
    (net (code "98") (name "Net-(Relay11-Pad1)") (class "Default")
      (node (ref "Relay11") (pin "1") (pinfunction "1_1") (pintype "passive"))
      (node (ref "U11") (pin "4") (pinfunction "C_4") (pintype "passive"))
    )
    (net (code "99") (name "Net-(Relay12-NC)") (class "Default")
      (node (ref "P25") (pin "3") (pinfunction "3_3") (pintype "passive"))
      (node (ref "Relay12") (pin "2") (pinfunction "NC_2") (pintype "passive"))
    )
    (net (code "100") (name "Net-(Relay12-NO)") (class "Default")
      (node (ref "P25") (pin "1") (pinfunction "1_1") (pintype "passive"))
      (node (ref "Relay12") (pin "4") (pinfunction "NO_4") (pintype "passive"))
    )
    (net (code "101") (name "Net-(Relay12-Pad1)") (class "Default")
      (node (ref "Relay12") (pin "1") (pinfunction "1_1") (pintype "passive"))
      (node (ref "U12") (pin "4") (pinfunction "C_4") (pintype "passive"))
    )
    (net (code "102") (name "Net-(Relay13-NC)") (class "Default")
      (node (ref "P28") (pin "1") (pinfunction "1_1") (pintype "passive"))
      (node (ref "Relay13") (pin "2") (pinfunction "NC_2") (pintype "passive"))
    )
    (net (code "103") (name "Net-(Relay13-NO)") (class "Default")
      (node (ref "P28") (pin "3") (pinfunction "3_3") (pintype "passive"))
      (node (ref "Relay13") (pin "4") (pinfunction "NO_4") (pintype "passive"))
    )
    (net (code "104") (name "Net-(Relay13-Pad1)") (class "Default")
      (node (ref "Relay13") (pin "1") (pinfunction "1_1") (pintype "passive"))
      (node (ref "U13") (pin "4") (pinfunction "C_4") (pintype "passive"))
    )
    (net (code "105") (name "Net-(Relay14-NC)") (class "Default")
      (node (ref "P30") (pin "3") (pinfunction "3_3") (pintype "passive"))
      (node (ref "Relay14") (pin "2") (pinfunction "NC_2") (pintype "passive"))
    )
    (net (code "106") (name "Net-(Relay14-NO)") (class "Default")
      (node (ref "P30") (pin "1") (pinfunction "1_1") (pintype "passive"))
      (node (ref "Relay14") (pin "4") (pinfunction "NO_4") (pintype "passive"))
    )
    (net (code "107") (name "Net-(Relay14-Pad1)") (class "Default")
      (node (ref "Relay14") (pin "1") (pinfunction "1_1") (pintype "passive"))
      (node (ref "U14") (pin "4") (pinfunction "C_4") (pintype "passive"))
    )
    (net (code "108") (name "Net-(Relay15-NC)") (class "Default")
      (node (ref "P31") (pin "1") (pinfunction "1_1") (pintype "passive"))
      (node (ref "Relay15") (pin "2") (pinfunction "NC_2") (pintype "passive"))
    )
    (net (code "109") (name "Net-(Relay15-NO)") (class "Default")
      (node (ref "P31") (pin "3") (pinfunction "3_3") (pintype "passive"))
      (node (ref "Relay15") (pin "4") (pinfunction "NO_4") (pintype "passive"))
    )
    (net (code "110") (name "Net-(Relay15-Pad1)") (class "Default")
      (node (ref "Relay15") (pin "1") (pinfunction "1_1") (pintype "passive"))
      (node (ref "U15") (pin "4") (pinfunction "C_4") (pintype "passive"))
    )
    (net (code "111") (name "Net-(Relay16-NC)") (class "Default")
      (node (ref "P33") (pin "3") (pinfunction "3_3") (pintype "passive"))
      (node (ref "Relay16") (pin "2") (pinfunction "NC_2") (pintype "passive"))
    )
    (net (code "112") (name "Net-(Relay16-NO)") (class "Default")
      (node (ref "P33") (pin "1") (pinfunction "1_1") (pintype "passive"))
      (node (ref "Relay16") (pin "4") (pinfunction "NO_4") (pintype "passive"))
    )
    (net (code "113") (name "Net-(Relay16-Pad1)") (class "Default")
      (node (ref "Relay16") (pin "1") (pinfunction "1_1") (pintype "passive"))
      (node (ref "U16") (pin "4") (pinfunction "C_4") (pintype "passive"))
    )
    (net (code "114") (name "Net-(U1-A)") (class "Default")
      (node (ref "R1") (pin "2") (pinfunction "2_2") (pintype "passive"))
      (node (ref "U1") (pin "1") (pinfunction "A_1") (pintype "passive"))
    )
    (net (code "115") (name "Net-(U2-A)") (class "Default")
      (node (ref "R2") (pin "2") (pinfunction "2_2") (pintype "passive"))
      (node (ref "U2") (pin "1") (pinfunction "A_1") (pintype "passive"))
    )
    (net (code "116") (name "Net-(U3-A)") (class "Default")
      (node (ref "R3") (pin "2") (pinfunction "2_2") (pintype "passive"))
      (node (ref "U3") (pin "1") (pinfunction "A_1") (pintype "passive"))
    )
    (net (code "117") (name "Net-(U4-A)") (class "Default")
      (node (ref "R4") (pin "2") (pinfunction "2_2") (pintype "passive"))
      (node (ref "U4") (pin "1") (pinfunction "A_1") (pintype "passive"))
    )
    (net (code "118") (name "Net-(U5-A)") (class "Default")
      (node (ref "R5") (pin "2") (pinfunction "2_2") (pintype "passive"))
      (node (ref "U5") (pin "1") (pinfunction "A_1") (pintype "passive"))
    )
    (net (code "119") (name "Net-(U6-A)") (class "Default")
      (node (ref "R6") (pin "2") (pinfunction "2_2") (pintype "passive"))
      (node (ref "U6") (pin "1") (pinfunction "A_1") (pintype "passive"))
    )
    (net (code "120") (name "Net-(U7-A)") (class "Default")
      (node (ref "R13") (pin "2") (pinfunction "2_2") (pintype "passive"))
      (node (ref "U7") (pin "1") (pinfunction "A_1") (pintype "passive"))
    )
    (net (code "121") (name "Net-(U8-A)") (class "Default")
      (node (ref "R14") (pin "2") (pinfunction "2_2") (pintype "passive"))
      (node (ref "U8") (pin "1") (pinfunction "A_1") (pintype "passive"))
    )
    (net (code "122") (name "Net-(U9-A)") (class "Default")
      (node (ref "R15") (pin "2") (pinfunction "2_2") (pintype "passive"))
      (node (ref "U9") (pin "1") (pinfunction "A_1") (pintype "passive"))
    )
    (net (code "123") (name "Net-(U10-A)") (class "Default")
      (node (ref "R16") (pin "2") (pinfunction "2_2") (pintype "passive"))
      (node (ref "U10") (pin "1") (pinfunction "A_1") (pintype "passive"))
    )
    (net (code "124") (name "Net-(U11-A)") (class "Default")
      (node (ref "R17") (pin "2") (pinfunction "2_2") (pintype "passive"))
      (node (ref "U11") (pin "1") (pinfunction "A_1") (pintype "passive"))
    )
    (net (code "125") (name "Net-(U12-A)") (class "Default")
      (node (ref "R18") (pin "2") (pinfunction "2_2") (pintype "passive"))
      (node (ref "U12") (pin "1") (pinfunction "A_1") (pintype "passive"))
    )
    (net (code "126") (name "Net-(U13-A)") (class "Default")
      (node (ref "R25") (pin "2") (pinfunction "2_2") (pintype "passive"))
      (node (ref "U13") (pin "1") (pinfunction "A_1") (pintype "passive"))
    )
    (net (code "127") (name "Net-(U14-A)") (class "Default")
      (node (ref "R26") (pin "2") (pinfunction "2_2") (pintype "passive"))
      (node (ref "U14") (pin "1") (pinfunction "A_1") (pintype "passive"))
    )
    (net (code "128") (name "Net-(U15-A)") (class "Default")
      (node (ref "R27") (pin "2") (pinfunction "2_2") (pintype "passive"))
      (node (ref "U15") (pin "1") (pinfunction "A_1") (pintype "passive"))
    )
    (net (code "129") (name "Net-(U16-A)") (class "Default")
      (node (ref "R28") (pin "2") (pinfunction "2_2") (pintype "passive"))
      (node (ref "U16") (pin "1") (pinfunction "A_1") (pintype "passive"))
    )
    (net (code "130") (name "VCC") (class "Default")
      (node (ref "C1") (pin "2") (pinfunction "2_2") (pintype "passive"))
      (node (ref "D1") (pin "2") (pinfunction "K_2") (pintype "passive"))
      (node (ref "P1") (pin "2") (pinfunction "2_2") (pintype "passive"))
      (node (ref "Relay1") (pin "8") (pinfunction "8_8") (pintype "passive"))
      (node (ref "Relay10") (pin "8") (pinfunction "8_8") (pintype "passive"))
      (node (ref "Relay11") (pin "8") (pinfunction "8_8") (pintype "passive"))
      (node (ref "Relay12") (pin "8") (pinfunction "8_8") (pintype "passive"))
      (node (ref "Relay13") (pin "8") (pinfunction "8_8") (pintype "passive"))
      (node (ref "Relay14") (pin "8") (pinfunction "8_8") (pintype "passive"))
      (node (ref "Relay15") (pin "8") (pinfunction "8_8") (pintype "passive"))
      (node (ref "Relay16") (pin "8") (pinfunction "8_8") (pintype "passive"))
      (node (ref "Relay2") (pin "8") (pinfunction "8_8") (pintype "passive"))
      (node (ref "Relay3") (pin "8") (pinfunction "8_8") (pintype "passive"))
      (node (ref "Relay4") (pin "8") (pinfunction "8_8") (pintype "passive"))
      (node (ref "Relay5") (pin "8") (pinfunction "8_8") (pintype "passive"))
      (node (ref "Relay6") (pin "8") (pinfunction "8_8") (pintype "passive"))
      (node (ref "Relay7") (pin "8") (pinfunction "8_8") (pintype "passive"))
      (node (ref "Relay8") (pin "8") (pinfunction "8_8") (pintype "passive"))
      (node (ref "Relay9") (pin "8") (pinfunction "8_8") (pintype "passive"))
    )
    (net (code "131") (name "unconnected-(Relay1-Pad5)") (class "Default")
      (node (ref "Relay1") (pin "5") (pinfunction "5_5") (pintype "passive"))
    )
    (net (code "132") (name "unconnected-(Relay1-Pad6)") (class "Default")
      (node (ref "Relay1") (pin "6") (pinfunction "6_6") (pintype "passive"))
    )
    (net (code "133") (name "unconnected-(Relay1-Pad7)") (class "Default")
      (node (ref "Relay1") (pin "7") (pinfunction "7_7") (pintype "passive"))
    )
    (net (code "134") (name "unconnected-(Relay2-Pad5)") (class "Default")
      (node (ref "Relay2") (pin "5") (pinfunction "5_5") (pintype "passive"))
    )
    (net (code "135") (name "unconnected-(Relay2-Pad6)") (class "Default")
      (node (ref "Relay2") (pin "6") (pinfunction "6_6") (pintype "passive"))
    )
    (net (code "136") (name "unconnected-(Relay2-Pad7)") (class "Default")
      (node (ref "Relay2") (pin "7") (pinfunction "7_7") (pintype "passive"))
    )
    (net (code "137") (name "unconnected-(Relay3-Pad5)") (class "Default")
      (node (ref "Relay3") (pin "5") (pinfunction "5_5") (pintype "passive"))
    )
    (net (code "138") (name "unconnected-(Relay3-Pad6)") (class "Default")
      (node (ref "Relay3") (pin "6") (pinfunction "6_6") (pintype "passive"))
    )
    (net (code "139") (name "unconnected-(Relay3-Pad7)") (class "Default")
      (node (ref "Relay3") (pin "7") (pinfunction "7_7") (pintype "passive"))
    )
    (net (code "140") (name "unconnected-(Relay4-Pad5)") (class "Default")
      (node (ref "Relay4") (pin "5") (pinfunction "5_5") (pintype "passive"))
    )
    (net (code "141") (name "unconnected-(Relay4-Pad6)") (class "Default")
      (node (ref "Relay4") (pin "6") (pinfunction "6_6") (pintype "passive"))
    )
    (net (code "142") (name "unconnected-(Relay4-Pad7)") (class "Default")
      (node (ref "Relay4") (pin "7") (pinfunction "7_7") (pintype "passive"))
    )
    (net (code "143") (name "unconnected-(Relay5-Pad5)") (class "Default")
      (node (ref "Relay5") (pin "5") (pinfunction "5_5") (pintype "passive"))
    )
    (net (code "144") (name "unconnected-(Relay5-Pad6)") (class "Default")
      (node (ref "Relay5") (pin "6") (pinfunction "6_6") (pintype "passive"))
    )
    (net (code "145") (name "unconnected-(Relay5-Pad7)") (class "Default")
      (node (ref "Relay5") (pin "7") (pinfunction "7_7") (pintype "passive"))
    )
    (net (code "146") (name "unconnected-(Relay6-Pad5)") (class "Default")
      (node (ref "Relay6") (pin "5") (pinfunction "5_5") (pintype "passive"))
    )
    (net (code "147") (name "unconnected-(Relay6-Pad6)") (class "Default")
      (node (ref "Relay6") (pin "6") (pinfunction "6_6") (pintype "passive"))
    )
    (net (code "148") (name "unconnected-(Relay6-Pad7)") (class "Default")
      (node (ref "Relay6") (pin "7") (pinfunction "7_7") (pintype "passive"))
    )
    (net (code "149") (name "unconnected-(Relay7-Pad5)") (class "Default")
      (node (ref "Relay7") (pin "5") (pinfunction "5_5") (pintype "passive"))
    )
    (net (code "150") (name "unconnected-(Relay7-Pad6)") (class "Default")
      (node (ref "Relay7") (pin "6") (pinfunction "6_6") (pintype "passive"))
    )
    (net (code "151") (name "unconnected-(Relay7-Pad7)") (class "Default")
      (node (ref "Relay7") (pin "7") (pinfunction "7_7") (pintype "passive"))
    )
    (net (code "152") (name "unconnected-(Relay8-Pad5)") (class "Default")
      (node (ref "Relay8") (pin "5") (pinfunction "5_5") (pintype "passive"))
    )
    (net (code "153") (name "unconnected-(Relay8-Pad6)") (class "Default")
      (node (ref "Relay8") (pin "6") (pinfunction "6_6") (pintype "passive"))
    )
    (net (code "154") (name "unconnected-(Relay8-Pad7)") (class "Default")
      (node (ref "Relay8") (pin "7") (pinfunction "7_7") (pintype "passive"))
    )
    (net (code "155") (name "unconnected-(Relay9-Pad5)") (class "Default")
      (node (ref "Relay9") (pin "5") (pinfunction "5_5") (pintype "passive"))
    )
    (net (code "156") (name "unconnected-(Relay9-Pad6)") (class "Default")
      (node (ref "Relay9") (pin "6") (pinfunction "6_6") (pintype "passive"))
    )
    (net (code "157") (name "unconnected-(Relay9-Pad7)") (class "Default")
      (node (ref "Relay9") (pin "7") (pinfunction "7_7") (pintype "passive"))
    )
    (net (code "158") (name "unconnected-(Relay10-Pad5)") (class "Default")
      (node (ref "Relay10") (pin "5") (pinfunction "5_5") (pintype "passive"))
    )
    (net (code "159") (name "unconnected-(Relay10-Pad6)") (class "Default")
      (node (ref "Relay10") (pin "6") (pinfunction "6_6") (pintype "passive"))
    )
    (net (code "160") (name "unconnected-(Relay10-Pad7)") (class "Default")
      (node (ref "Relay10") (pin "7") (pinfunction "7_7") (pintype "passive"))
    )
    (net (code "161") (name "unconnected-(Relay11-Pad5)") (class "Default")
      (node (ref "Relay11") (pin "5") (pinfunction "5_5") (pintype "passive"))
    )
    (net (code "162") (name "unconnected-(Relay11-Pad6)") (class "Default")
      (node (ref "Relay11") (pin "6") (pinfunction "6_6") (pintype "passive"))
    )
    (net (code "163") (name "unconnected-(Relay11-Pad7)") (class "Default")
      (node (ref "Relay11") (pin "7") (pinfunction "7_7") (pintype "passive"))
    )
    (net (code "164") (name "unconnected-(Relay12-Pad5)") (class "Default")
      (node (ref "Relay12") (pin "5") (pinfunction "5_5") (pintype "passive"))
    )
    (net (code "165") (name "unconnected-(Relay12-Pad6)") (class "Default")
      (node (ref "Relay12") (pin "6") (pinfunction "6_6") (pintype "passive"))
    )
    (net (code "166") (name "unconnected-(Relay12-Pad7)") (class "Default")
      (node (ref "Relay12") (pin "7") (pinfunction "7_7") (pintype "passive"))
    )
    (net (code "167") (name "unconnected-(Relay13-Pad5)") (class "Default")
      (node (ref "Relay13") (pin "5") (pinfunction "5_5") (pintype "passive"))
    )
    (net (code "168") (name "unconnected-(Relay13-Pad6)") (class "Default")
      (node (ref "Relay13") (pin "6") (pinfunction "6_6") (pintype "passive"))
    )
    (net (code "169") (name "unconnected-(Relay13-Pad7)") (class "Default")
      (node (ref "Relay13") (pin "7") (pinfunction "7_7") (pintype "passive"))
    )
    (net (code "170") (name "unconnected-(Relay14-Pad5)") (class "Default")
      (node (ref "Relay14") (pin "5") (pinfunction "5_5") (pintype "passive"))
    )
    (net (code "171") (name "unconnected-(Relay14-Pad6)") (class "Default")
      (node (ref "Relay14") (pin "6") (pinfunction "6_6") (pintype "passive"))
    )
    (net (code "172") (name "unconnected-(Relay14-Pad7)") (class "Default")
      (node (ref "Relay14") (pin "7") (pinfunction "7_7") (pintype "passive"))
    )
    (net (code "173") (name "unconnected-(Relay15-Pad5)") (class "Default")
      (node (ref "Relay15") (pin "5") (pinfunction "5_5") (pintype "passive"))
    )
    (net (code "174") (name "unconnected-(Relay15-Pad6)") (class "Default")
      (node (ref "Relay15") (pin "6") (pinfunction "6_6") (pintype "passive"))
    )
    (net (code "175") (name "unconnected-(Relay15-Pad7)") (class "Default")
      (node (ref "Relay15") (pin "7") (pinfunction "7_7") (pintype "passive"))
    )
    (net (code "176") (name "unconnected-(Relay16-Pad5)") (class "Default")
      (node (ref "Relay16") (pin "5") (pinfunction "5_5") (pintype "passive"))
    )
    (net (code "177") (name "unconnected-(Relay16-Pad6)") (class "Default")
      (node (ref "Relay16") (pin "6") (pinfunction "6_6") (pintype "passive"))
    )
    (net (code "178") (name "unconnected-(Relay16-Pad7)") (class "Default")
      (node (ref "Relay16") (pin "7") (pinfunction "7_7") (pintype "passive"))
    )
  )
)
